# 03_NOTECARD-CONNECTION.net
KiCad netlist of a schematic drawn in Altium Designer
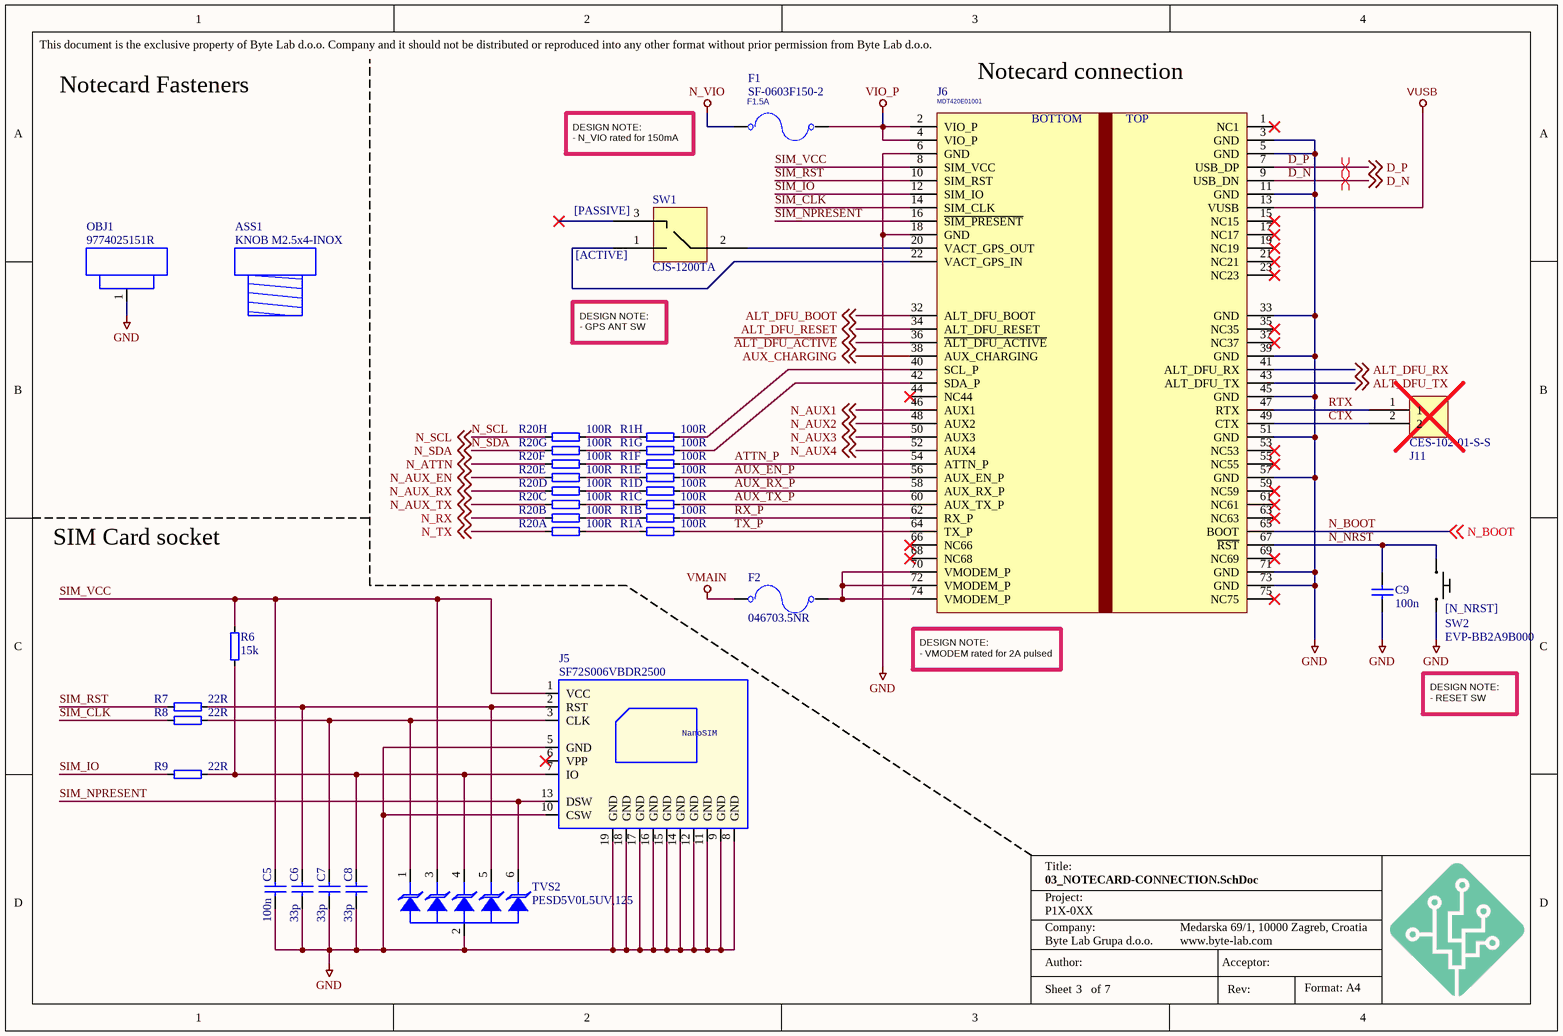
[diagram p0: 03_NOTECARD-CONNECTION.SchDoc]

(export (version "E")
  (design (tool "Eeschema 10.0.6"))
  (components
    (comp (ref "ASS1")
      (value "KNOB M2.5x4-INOX")
      (description "VITE TCEI 2.5X4 ESAGONO INCASSATO A2 INOX")
      (fields
        (field (name "MANUFACTURER PART NUMBER") "M2.5X4/D7985-A2")
        (field (name "MANUFACTURER") "KRAFTBERG")
        (field (name "DRAWN_BY") "Blues Wireless")
      )
      (libsource (lib "n21-p2") (part "KNOB - M2.5x4-INOX"))
    )
    (comp (ref "C5")
      (value "100n")
      (footprint "C-0402")
      (description "Capacitor ceramic 100n ±10% X7R 16V 0402")
      (fields
        (field (name "BL PART NUMBER") "2000-908")
        (field (name "DRAWN_BY") "Puskar")
        (field (name "CHECKED_BY") "Dodig")
      )
      (libsource (lib "BL_Passive") (part "C0402-100n-16V-X7R"))
    )
    (comp (ref "C6")
      (value "33p")
      (footprint "C-0402")
      (description "Capacitor ceramic 33p ±5% C0G 50V 0402")
      (fields
        (field (name "BL PART NUMBER") "2001-377")
        (field (name "DRAWN_BY") "Puskar")
        (field (name "CHECKED_BY") "Dodig")
      )
      (libsource (lib "BL_Passive") (part "C0402-33p-50V-C0G-5"))
    )
    (comp (ref "C7")
      (value "33p")
      (footprint "C-0402")
      (description "Capacitor ceramic 33p ±5% C0G 50V 0402")
      (fields
        (field (name "BL PART NUMBER") "2001-377")
        (field (name "DRAWN_BY") "Puskar")
        (field (name "CHECKED_BY") "Dodig")
      )
      (libsource (lib "BL_Passive") (part "C0402-33p-50V-C0G-5"))
    )
    (comp (ref "C8")
      (value "33p")
      (footprint "C-0402")
      (description "Capacitor ceramic 33p ±5% C0G 50V 0402")
      (fields
        (field (name "BL PART NUMBER") "2001-377")
        (field (name "DRAWN_BY") "Puskar")
        (field (name "CHECKED_BY") "Dodig")
      )
      (libsource (lib "BL_Passive") (part "C0402-33p-50V-C0G-5"))
    )
    (comp (ref "C9")
      (value "100n")
      (footprint "C-0402")
      (description "Capacitor ceramic 100n ±10% X7R 16V 0402")
      (fields
        (field (name "BL PART NUMBER") "2000-908")
        (field (name "DRAWN_BY") "Puskar")
        (field (name "CHECKED_BY") "Dodig")
      )
      (libsource (lib "BL_Passive") (part "C0402-100n-16V-X7R"))
    )
    (comp (ref "F1")
      (value "SF-0603F150-2")
      (footprint "FS-0603")
      (description "FUSIBILE RAPIDO 1.5A 32V 0603 SF-0603F150-2 BOURNS SMT")
      (fields
        (field (name "MANUFACTURER") "Bourns Inc.")
        (field (name "BL PART NUMBER") "2007-468")
        (field (name "DRAWN_BY") "Blues Wireless")
      )
      (libsource (lib "n21-p2") (part "RAPIDO - SF-0603F150-2-1.5A/32V"))
    )
    (comp (ref "F2")
      (value "046703.5NR")
      (footprint "FS-0603")
      (description "Fuse Chip Very Fast Acting 3.5A 32V SMD Solder Pad 0603 T/R CSA")
      (fields
        (field (name "MANUFACTURER") "Littelfuse Inc.")
        (field (name "BL PART NUMBER") "2007-469")
        (field (name "DRAWN_BY") "Blues Wireless")
      )
      (libsource (lib "n21-p2") (part "046703.5NR"))
    )
    (comp (ref "J5")
      (value "SF72S006VBDR2500")
      (footprint "J-NANOSIM-SF72S006VBA")
      (description "CONN. NANOSIM 8P F/90° PUSH-PUSH SF72S006VBAR2500 JAE ELECTRONICS SMT")
      (fields
        (field (name "MANUFACTURER") "JAE Electronics")
        (field (name "BL PART NUMBER") "2007-458")
        (field (name "DRAWN_BY") "Blues Wireless")
      )
      (libsource (lib "n21-p2") (part "NANOSIM - J-NANOSIM-SF72S006VBA"))
    )
    (comp (ref "J6")
      (value "MDT420E01001")
      (footprint "J-75-0050-MOS-M2")
      (description "CONN. M.2 75P M/90° P=0.5 MDT420E01001 AMPHENOL SMT")
      (fields
        (field (name "MANUFACTURER") "Amphenol ICC (FCI)")
        (field (name "MANUFACTURER PART NUMBER") "MDT420E03001")
        (field (name "DRAWN_BY") "Blues Wireless")
      )
      (libsource (lib "n21-p2") (part "AMPHENOL-75 - M-2 KEY E_13"))
    )
    (comp (ref "J11")
      (value "CES-102-01-S-S")
      (footprint "CONN_02")
      (description "0,1\" 2 PIN Header")
      (fields
        (field (name "MANUFACTURER") "Samtec Inc.")
        (field (name "BL PART NUMBER") "2007-461")
        (field (name "DRAWN_BY") "Blues Wireless")
      )
      (libsource (lib "n21-p2") (part "CONN_02"))
    )
    (comp (ref "OBJ1")
      (value "9774025151R")
      (footprint "DIST-WASMSIM0250")
      (description "DISTANZ. CIL. METALLO 5.1X2.5 9774025151R W.E SMT")
      (fields
        (field (name "MANUFACTURER") "Würth Elektronik")
        (field (name "BL PART NUMBER") "6020-113")
        (field (name "DRAWN_BY") "Blues Wieless")
      )
      (libsource (lib "n21-p2") (part "DISTANZIALE - M2.5x0250"))
    )
    (comp (ref "R1")
      (value "100R")
      (footprint "BL_Passive:RESCAXS80P640X160X50-16N")
      (description "Resistor array 100R 5% 2506")
      (fields
        (field (name "MANUFACTURER PART NUMBER") "742C163101JP")
        (field (name "MANUFACTURER") "CTS Resistor Products")
        (field (name "CHECKED_BY") "*")
        (field (name "DRAWN_BY") "Hamin")
      )
      (libsource (lib "BL_Passive") (part "RESCAXS80P640X160X50-16N - 8x100R"))
    )
    (comp (ref "R6")
      (value "15k")
      (footprint "BL_Passive:R-0402")
      (description "Resistor 15k ±1% 0402")
      (fields
        (field (name "BL PART NUMBER") "2001-157")
        (field (name "CHECKED_BY") "Zvonc")
        (field (name "DRAWN_BY") "Puskar")
      )
      (libsource (lib "BL_Passive") (part "R0402-15k-1"))
    )
    (comp (ref "R7")
      (value "22R")
      (footprint "BL_Passive:R-0402")
      (description "Resistor 22R ±1% 0402")
      (fields
        (field (name "BL PART NUMBER") "2001-170")
        (field (name "CHECKED_BY") "Hamin")
        (field (name "DRAWN_BY") "Zvonc")
      )
      (libsource (lib "BL_Passive") (part "R0402-22R-1"))
    )
    (comp (ref "R8")
      (value "22R")
      (footprint "BL_Passive:R-0402")
      (description "Resistor 22R ±1% 0402")
      (fields
        (field (name "BL PART NUMBER") "2001-170")
        (field (name "CHECKED_BY") "Hamin")
        (field (name "DRAWN_BY") "Zvonc")
      )
      (libsource (lib "BL_Passive") (part "R0402-22R-1"))
    )
    (comp (ref "R9")
      (value "22R")
      (footprint "BL_Passive:R-0402")
      (description "Resistor 22R ±1% 0402")
      (fields
        (field (name "BL PART NUMBER") "2001-170")
        (field (name "CHECKED_BY") "Hamin")
        (field (name "DRAWN_BY") "Zvonc")
      )
      (libsource (lib "BL_Passive") (part "R0402-22R-1"))
    )
    (comp (ref "R20")
      (value "100R")
      (footprint "BL_Passive:RESCAXS80P640X160X50-16N")
      (description "Resistor array 100R 5% 2506")
      (fields
        (field (name "MANUFACTURER PART NUMBER") "742C163101JP")
        (field (name "MANUFACTURER") "CTS Resistor Products")
        (field (name "CHECKED_BY") "*")
        (field (name "DRAWN_BY") "Hamin")
      )
      (libsource (lib "BL_Passive") (part "RESCAXS80P640X160X50-16N - 8x100R"))
    )
    (comp (ref "SW1")
      (value "CJS-1200TA")
      (footprint "SW_CJS-1200TA")
      (description "Switch Slide N.O./N.C. SPDT Raised Slide 0.1A 24VDC J-Hook SMD Embossed T/R")
      (fields
        (field (name "MANUFACTURER") "Nidec Copal")
        (field (name "BL PART NUMBER") "2007-456")
        (field (name "DRAWN_BY") "Blues Wireless")
      )
      (libsource (lib "n21-p2") (part "CJS-1200TA"))
    )
    (comp (ref "SW2")
      (value "EVP-BB2A9B000")
      (footprint "BL_Mechanical:SW_EVP-BB2A9B000")
      (description "SWITCH TACTILE SPST-NO 0.05A 15V")
      (fields
        (field (name "MANUFACTURER") "Panasonic Electronic Components")
        (field (name "BL PART NUMBER") "2007-124")
        (field (name "DRAWN_BY") "Marsic")
        (field (name "CHECKED_BY") "*")
      )
      (libsource (lib "BL_Mechanical") (part "Switch tact EVP-BB2A9B000"))
    )
    (comp (ref "TVS2")
      (value "PESD5V0L5UV,125")
      (footprint "SOT666")
      (description "PESD Series 25 W 5 V Uni-Directional Fivefold ESD Protection Diode Array SOT-666")
      (fields
        (field (name "MANUFACTURER") "Nexperia")
        (field (name "BL PART NUMBER") "2007-452")
        (field (name "DRAWN_BY") "Blues Wireless")
      )
      (libsource (lib "n21-p2") (part "PESD5V0L5UV,125"))
    )
  )
  (nets
    (net (code "1") (name "/ATTN_P") (class "Default")
      (node (ref "J6") (pin "54") (pinfunction "ATTN_P_54") (pintype "passive"))
      (node (ref "R1") (pin "11") (pintype "passive"))
    )
    (net (code "2") (name "/AUX_EN_P") (class "Default")
      (node (ref "J6") (pin "56") (pinfunction "AUX_EN_P_56") (pintype "passive"))
      (node (ref "R1") (pin "12") (pintype "passive"))
    )
    (net (code "3") (name "/AUX_RX_P") (class "Default")
      (node (ref "J6") (pin "58") (pinfunction "AUX_RX_P_58") (pintype "passive"))
      (node (ref "R1") (pin "13") (pintype "passive"))
    )
    (net (code "4") (name "/AUX_TX_P") (class "Default")
      (node (ref "J6") (pin "60") (pinfunction "AUX_TX_P_60") (pintype "passive"))
      (node (ref "R1") (pin "14") (pintype "passive"))
    )
    (net (code "5") (name "/CTX") (class "Default")
      (node (ref "J11") (pin "2") (pinfunction "2_2") (pintype "passive"))
      (node (ref "J6") (pin "49") (pinfunction "CTX_49") (pintype "passive"))
    )
    (net (code "6") (name "/N_NRST") (class "Default")
      (node (ref "C9") (pin "2") (pinfunction "2_2") (pintype "passive"))
      (node (ref "J6") (pin "67") (pinfunction "~{RST}_67") (pintype "passive"))
      (node (ref "SW2") (pin "1") (pinfunction "A_1") (pintype "passive"))
    )
    (net (code "7") (name "/RTX") (class "Default")
      (node (ref "J11") (pin "1") (pinfunction "1_1") (pintype "passive"))
      (node (ref "J6") (pin "47") (pinfunction "RTX_47") (pintype "passive"))
    )
    (net (code "8") (name "/RX_P") (class "Default")
      (node (ref "J6") (pin "62") (pinfunction "RX_P_62") (pintype "passive"))
      (node (ref "R1") (pin "15") (pintype "passive"))
    )
    (net (code "9") (name "/SIM_CLK") (class "Default")
      (node (ref "J6") (pin "14") (pinfunction "SIM_CLK_14") (pintype "passive"))
      (node (ref "R8") (pin "1") (pintype "passive"))
    )
    (net (code "10") (name "/SIM_IO") (class "Default")
      (node (ref "J6") (pin "12") (pinfunction "SIM_IO_12") (pintype "passive"))
      (node (ref "R9") (pin "1") (pintype "passive"))
    )
    (net (code "11") (name "/SIM_NPRESENT") (class "Default")
      (node (ref "J5") (pin "13") (pinfunction "DSW_13") (pintype "passive"))
      (node (ref "J6") (pin "16") (pinfunction "~{SIM_PRESENT}_16") (pintype "passive"))
      (node (ref "TVS2") (pin "6") (pinfunction "C6_6") (pintype "passive"))
    )
    (net (code "12") (name "/SIM_RST") (class "Default")
      (node (ref "J6") (pin "10") (pinfunction "SIM_RST_10") (pintype "passive"))
      (node (ref "R7") (pin "1") (pintype "passive"))
    )
    (net (code "13") (name "/SIM_VCC") (class "Default")
      (node (ref "C5") (pin "2") (pinfunction "2_2") (pintype "passive"))
      (node (ref "J5") (pin "1") (pinfunction "VCC_1") (pintype "power_in"))
      (node (ref "J6") (pin "8") (pinfunction "SIM_VCC_8") (pintype "passive"))
      (node (ref "R6") (pin "2") (pintype "passive"))
      (node (ref "TVS2") (pin "3") (pinfunction "C3_3") (pintype "passive"))
    )
    (net (code "14") (name "/TX_P") (class "Default")
      (node (ref "J6") (pin "64") (pinfunction "TX_P_64") (pintype "passive"))
      (node (ref "R1") (pin "16") (pintype "passive"))
    )
    (net (code "15") (name "ALT_DFU_ACTIVE") (class "Default")
      (node (ref "J6") (pin "36") (pinfunction "~{ALT_DFU_ACTIVE}_36") (pintype "passive"))
    )
    (net (code "16") (name "ALT_DFU_BOOT") (class "Default")
      (node (ref "J6") (pin "32") (pinfunction "ALT_DFU_BOOT_32") (pintype "passive"))
    )
    (net (code "17") (name "ALT_DFU_RESET") (class "Default")
      (node (ref "J6") (pin "34") (pinfunction "ALT_DFU_RESET_34") (pintype "passive"))
    )
    (net (code "18") (name "ALT_DFU_RX") (class "Default")
      (node (ref "J6") (pin "41") (pinfunction "ALT_DFU_RX_41") (pintype "passive"))
    )
    (net (code "19") (name "ALT_DFU_TX") (class "Default")
      (node (ref "J6") (pin "43") (pinfunction "ALT_DFU_TX_43") (pintype "passive"))
    )
    (net (code "20") (name "AUX_CHARGING") (class "Default")
      (node (ref "J6") (pin "38") (pinfunction "AUX_CHARGING_38") (pintype "passive"))
    )
    (net (code "21") (name "D_N") (class "Default")
      (node (ref "J6") (pin "9") (pinfunction "USB_DN_9") (pintype "passive"))
    )
    (net (code "22") (name "D_P") (class "Default")
      (node (ref "J6") (pin "7") (pinfunction "USB_DP_7") (pintype "passive"))
    )
    (net (code "23") (name "GND") (class "Default")
      (node (ref "C5") (pin "1") (pinfunction "1_1") (pintype "passive"))
      (node (ref "C6") (pin "1") (pinfunction "1_1") (pintype "passive"))
      (node (ref "C7") (pin "1") (pinfunction "1_1") (pintype "passive"))
      (node (ref "C8") (pin "1") (pinfunction "1_1") (pintype "passive"))
      (node (ref "C9") (pin "1") (pinfunction "1_1") (pintype "passive"))
      (node (ref "J5") (pin "10") (pinfunction "CSW_10") (pintype "passive"))
      (node (ref "J5") (pin "11") (pinfunction "GND_11") (pintype "power_in"))
      (node (ref "J5") (pin "12") (pinfunction "GND_12") (pintype "power_in"))
      (node (ref "J5") (pin "14") (pinfunction "GND_14") (pintype "power_in"))
      (node (ref "J5") (pin "15") (pinfunction "GND_15") (pintype "power_in"))
      (node (ref "J5") (pin "16") (pinfunction "GND_16") (pintype "power_in"))
      (node (ref "J5") (pin "17") (pinfunction "GND_17") (pintype "power_in"))
      (node (ref "J5") (pin "18") (pinfunction "GND_18") (pintype "power_in"))
      (node (ref "J5") (pin "19") (pinfunction "GND_19") (pintype "power_in"))
      (node (ref "J5") (pin "5") (pinfunction "GND_5") (pintype "power_in"))
      (node (ref "J5") (pin "8") (pinfunction "GND_8") (pintype "power_in"))
      (node (ref "J5") (pin "9") (pinfunction "GND_9") (pintype "power_in"))
      (node (ref "J6") (pin "11") (pinfunction "GND_11") (pintype "passive"))
      (node (ref "J6") (pin "18") (pinfunction "GND_18") (pintype "passive"))
      (node (ref "J6") (pin "3") (pinfunction "GND_3") (pintype "passive"))
      (node (ref "J6") (pin "33") (pinfunction "GND_33") (pintype "passive"))
      (node (ref "J6") (pin "39") (pinfunction "GND_39") (pintype "passive"))
      (node (ref "J6") (pin "45") (pinfunction "GND_45") (pintype "passive"))
      (node (ref "J6") (pin "5") (pinfunction "GND_5") (pintype "passive"))
      (node (ref "J6") (pin "51") (pinfunction "GND_51") (pintype "passive"))
      (node (ref "J6") (pin "57") (pinfunction "GND_57") (pintype "passive"))
      (node (ref "J6") (pin "6") (pinfunction "GND_6") (pintype "passive"))
      (node (ref "J6") (pin "71") (pinfunction "GND_71") (pintype "passive"))
      (node (ref "J6") (pin "73") (pinfunction "GND_73") (pintype "passive"))
      (node (ref "OBJ1") (pin "1") (pinfunction "1_1") (pintype "power_in"))
      (node (ref "SW2") (pin "2") (pinfunction "B_2") (pintype "passive"))
      (node (ref "TVS2") (pin "2") (pinfunction "A2_2") (pintype "passive"))
    )
    (net (code "24") (name "N_ATTN") (class "Default") (node (ref "R20") (pin "6") (pintype "passive")))
    (net (code "25") (name "N_AUX1") (class "Default")
      (node (ref "J6") (pin "46") (pinfunction "AUX1_46") (pintype "passive"))
    )
    (net (code "26") (name "N_AUX2") (class "Default")
      (node (ref "J6") (pin "48") (pinfunction "AUX2_48") (pintype "passive"))
    )
    (net (code "27") (name "N_AUX3") (class "Default")
      (node (ref "J6") (pin "50") (pinfunction "AUX3_50") (pintype "passive"))
    )
    (net (code "28") (name "N_AUX4") (class "Default")
      (node (ref "J6") (pin "52") (pinfunction "AUX4_52") (pintype "passive"))
    )
    (net (code "29") (name "N_AUX_EN") (class "Default") (node (ref "R20") (pin "5") (pintype "passive")))
    (net (code "30") (name "N_AUX_RX") (class "Default") (node (ref "R20") (pin "4") (pintype "passive")))
    (net (code "31") (name "N_AUX_TX") (class "Default") (node (ref "R20") (pin "3") (pintype "passive")))
    (net (code "32") (name "N_BOOT") (class "Default")
      (node (ref "J6") (pin "65") (pinfunction "BOOT_65") (pintype "passive"))
    )
    (net (code "33") (name "N_RX") (class "Default") (node (ref "R20") (pin "2") (pintype "passive")))
    (net (code "34") (name "N_SCL") (class "Default") (node (ref "R20") (pin "8") (pintype "passive")))
    (net (code "35") (name "N_SDA") (class "Default") (node (ref "R20") (pin "7") (pintype "passive")))
    (net (code "36") (name "N_TX") (class "Default") (node (ref "R20") (pin "1") (pintype "passive")))
    (net (code "37") (name "N_VIO") (class "Default")
      (node (ref "F1") (pin "1") (pinfunction "1_1") (pintype "passive"))
    )
    (net (code "38") (name "Net-(F2-Pad2)") (class "Default")
      (node (ref "F2") (pin "2") (pinfunction "2_2") (pintype "passive"))
      (node (ref "J6") (pin "70") (pinfunction "VMODEM_P_70") (pintype "passive"))
      (node (ref "J6") (pin "72") (pinfunction "VMODEM_P_72") (pintype "passive"))
      (node (ref "J6") (pin "74") (pinfunction "VMODEM_P_74") (pintype "passive"))
    )
    (net (code "39") (name "Net-(J5-CLK)") (class "Default")
      (node (ref "C7") (pin "2") (pinfunction "2_2") (pintype "passive"))
      (node (ref "J5") (pin "3") (pinfunction "CLK_3") (pintype "passive"))
      (node (ref "R8") (pin "2") (pintype "passive"))
      (node (ref "TVS2") (pin "1") (pinfunction "C1_1") (pintype "passive"))
    )
    (net (code "40") (name "Net-(J5-IO)") (class "Default")
      (node (ref "C8") (pin "2") (pinfunction "2_2") (pintype "passive"))
      (node (ref "J5") (pin "7") (pinfunction "IO_7") (pintype "bidirectional"))
      (node (ref "R6") (pin "1") (pintype "passive"))
      (node (ref "R9") (pin "2") (pintype "passive"))
      (node (ref "TVS2") (pin "4") (pinfunction "C4_4") (pintype "passive"))
    )
    (net (code "41") (name "Net-(J5-RST)") (class "Default")
      (node (ref "C6") (pin "2") (pinfunction "2_2") (pintype "passive"))
      (node (ref "J5") (pin "2") (pinfunction "RST_2") (pintype "passive"))
      (node (ref "R7") (pin "2") (pintype "passive"))
      (node (ref "TVS2") (pin "5") (pinfunction "A5_5") (pintype "passive"))
    )
    (net (code "42") (name "Net-(J6-SCL_P)") (class "Default")
      (node (ref "J6") (pin "40") (pinfunction "SCL_P_40") (pintype "passive"))
      (node (ref "R1") (pin "9") (pintype "passive"))
    )
    (net (code "43") (name "Net-(J6-SDA_P)") (class "Default")
      (node (ref "J6") (pin "42") (pinfunction "SDA_P_42") (pintype "passive"))
      (node (ref "R1") (pin "10") (pintype "passive"))
    )
    (net (code "44") (name "Net-(J6-VACT_GPS_IN)") (class "Default")
      (node (ref "J6") (pin "22") (pinfunction "VACT_GPS_IN_22") (pintype "passive"))
      (node (ref "SW1") (pin "1") (pinfunction "1_1") (pintype "passive"))
    )
    (net (code "45") (name "Net-(J6-VACT_GPS_OUT)") (class "Default")
      (node (ref "J6") (pin "20") (pinfunction "VACT_GPS_OUT_20") (pintype "passive"))
      (node (ref "SW1") (pin "2") (pinfunction "2_2") (pintype "passive"))
    )
    (net (code "46") (name "Net-(R1-Pad1)") (class "Default")
      (node (ref "R1") (pin "1") (pintype "passive"))
      (node (ref "R20") (pin "16") (pintype "passive"))
    )
    (net (code "47") (name "Net-(R1-Pad2)") (class "Default")
      (node (ref "R1") (pin "2") (pintype "passive"))
      (node (ref "R20") (pin "15") (pintype "passive"))
    )
    (net (code "48") (name "Net-(R1-Pad3)") (class "Default")
      (node (ref "R1") (pin "3") (pintype "passive"))
      (node (ref "R20") (pin "14") (pintype "passive"))
    )
    (net (code "49") (name "Net-(R1-Pad4)") (class "Default")
      (node (ref "R1") (pin "4") (pintype "passive"))
      (node (ref "R20") (pin "13") (pintype "passive"))
    )
    (net (code "50") (name "Net-(R1-Pad5)") (class "Default")
      (node (ref "R1") (pin "5") (pintype "passive"))
      (node (ref "R20") (pin "12") (pintype "passive"))
    )
    (net (code "51") (name "Net-(R1-Pad6)") (class "Default")
      (node (ref "R1") (pin "6") (pintype "passive"))
      (node (ref "R20") (pin "11") (pintype "passive"))
    )
    (net (code "52") (name "Net-(R1-Pad7)") (class "Default")
      (node (ref "R1") (pin "7") (pintype "passive"))
      (node (ref "R20") (pin "10") (pintype "passive"))
    )
    (net (code "53") (name "Net-(R1-Pad8)") (class "Default")
      (node (ref "R1") (pin "8") (pintype "passive"))
      (node (ref "R20") (pin "9") (pintype "passive"))
    )
    (net (code "54") (name "VIO_P") (class "Default")
      (node (ref "F1") (pin "2") (pinfunction "2_2") (pintype "passive"))
      (node (ref "J6") (pin "2") (pinfunction "VIO_P_2") (pintype "passive"))
      (node (ref "J6") (pin "4") (pinfunction "VIO_P_4") (pintype "passive"))
    )
    (net (code "55") (name "VMAIN") (class "Default")
      (node (ref "F2") (pin "1") (pinfunction "1_1") (pintype "passive"))
    )
    (net (code "56") (name "VUSB") (class "Default")
      (node (ref "J6") (pin "13") (pinfunction "VUSB_13") (pintype "passive"))
    )
    (net (code "57") (name "unconnected-(J5-VPP-Pad6)") (class "Default")
      (node (ref "J5") (pin "6") (pinfunction "VPP_6") (pintype "passive+no_connect"))
    )
    (net (code "58") (name "unconnected-(J6-NC1-Pad1)") (class "Default")
      (node (ref "J6") (pin "1") (pinfunction "NC1_1") (pintype "passive+no_connect"))
    )
    (net (code "59") (name "unconnected-(J6-NC15-Pad15)") (class "Default")
      (node (ref "J6") (pin "15") (pinfunction "NC15_15") (pintype "passive+no_connect"))
    )
    (net (code "60") (name "unconnected-(J6-NC17-Pad17)") (class "Default")
      (node (ref "J6") (pin "17") (pinfunction "NC17_17") (pintype "passive+no_connect"))
    )
    (net (code "61") (name "unconnected-(J6-NC19-Pad19)") (class "Default")
      (node (ref "J6") (pin "19") (pinfunction "NC19_19") (pintype "passive+no_connect"))
    )
    (net (code "62") (name "unconnected-(J6-NC21-Pad21)") (class "Default")
      (node (ref "J6") (pin "21") (pinfunction "NC21_21") (pintype "passive+no_connect"))
    )
    (net (code "63") (name "unconnected-(J6-NC23-Pad23)") (class "Default")
      (node (ref "J6") (pin "23") (pinfunction "NC23_23") (pintype "passive+no_connect"))
    )
    (net (code "64") (name "unconnected-(J6-NC35-Pad35)") (class "Default")
      (node (ref "J6") (pin "35") (pinfunction "NC35_35") (pintype "passive+no_connect"))
    )
    (net (code "65") (name "unconnected-(J6-NC37-Pad37)") (class "Default")
      (node (ref "J6") (pin "37") (pinfunction "NC37_37") (pintype "passive+no_connect"))
    )
    (net (code "66") (name "unconnected-(J6-NC44-Pad44)") (class "Default")
      (node (ref "J6") (pin "44") (pinfunction "NC44_44") (pintype "passive+no_connect"))
    )
    (net (code "67") (name "unconnected-(J6-NC53-Pad53)") (class "Default")
      (node (ref "J6") (pin "53") (pinfunction "NC53_53") (pintype "passive+no_connect"))
    )
    (net (code "68") (name "unconnected-(J6-NC55-Pad55)") (class "Default")
      (node (ref "J6") (pin "55") (pinfunction "NC55_55") (pintype "passive+no_connect"))
    )
    (net (code "69") (name "unconnected-(J6-NC59-Pad59)") (class "Default")
      (node (ref "J6") (pin "59") (pinfunction "NC59_59") (pintype "passive+no_connect"))
    )
    (net (code "70") (name "unconnected-(J6-NC61-Pad61)") (class "Default")
      (node (ref "J6") (pin "61") (pinfunction "NC61_61") (pintype "passive+no_connect"))
    )
    (net (code "71") (name "unconnected-(J6-NC63-Pad63)") (class "Default")
      (node (ref "J6") (pin "63") (pinfunction "NC63_63") (pintype "passive+no_connect"))
    )
    (net (code "72") (name "unconnected-(J6-NC66-Pad66)") (class "Default")
      (node (ref "J6") (pin "66") (pinfunction "NC66_66") (pintype "passive+no_connect"))
    )
    (net (code "73") (name "unconnected-(J6-NC68-Pad68)") (class "Default")
      (node (ref "J6") (pin "68") (pinfunction "NC68_68") (pintype "passive+no_connect"))
    )
    (net (code "74") (name "unconnected-(J6-NC69-Pad69)") (class "Default")
      (node (ref "J6") (pin "69") (pinfunction "NC69_69") (pintype "passive+no_connect"))
    )
    (net (code "75") (name "unconnected-(J6-NC75-Pad75)") (class "Default")
      (node (ref "J6") (pin "75") (pinfunction "NC75_75") (pintype "passive+no_connect"))
    )
    (net (code "76") (name "unconnected-(SW1-Pad3)") (class "Default")
      (node (ref "SW1") (pin "3") (pinfunction "3_3") (pintype "passive+no_connect"))
    )
  )
)
